# Emitter.net
KiCad netlist of a schematic drawn in Altium Designer
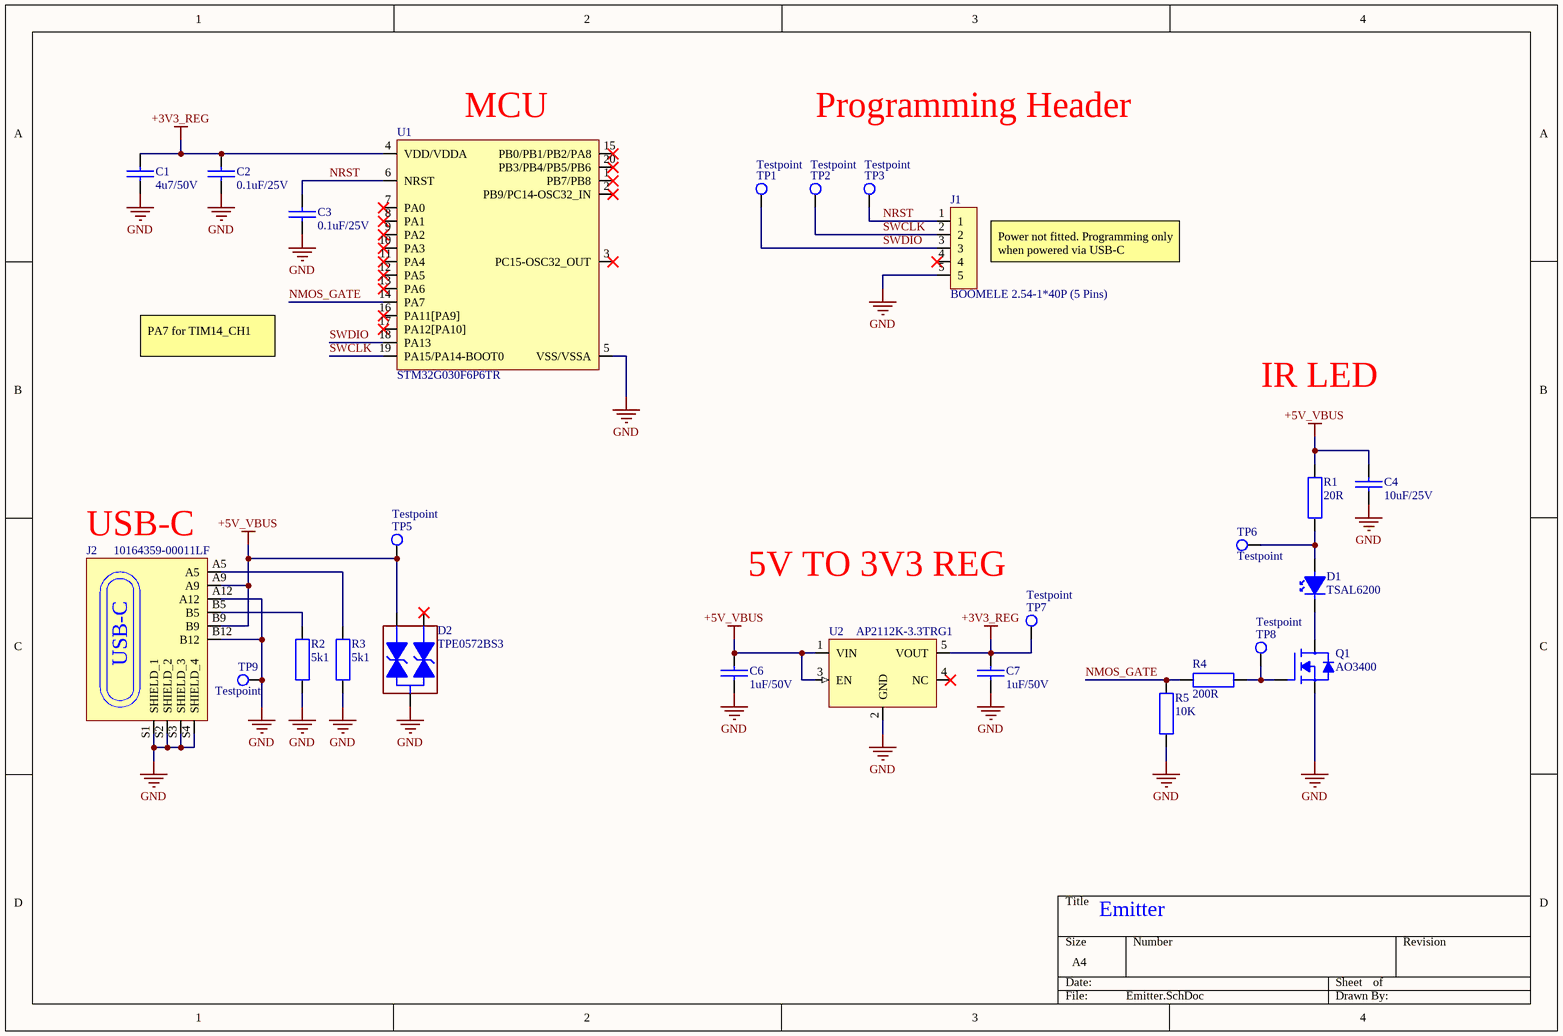
[diagram p0: Emitter.SchDoc]

(export (version "E")
  (design (tool "Eeschema 10.0.6"))
  (components
    (comp (ref "C1")
      (value "4u7/50V")
      (footprint "CAPC2012X95N")
      (description "CAP CER 4.7uF 50V X5R 0805")
      (fields
        (field (name "MANUFACTURER PART NUMBER") "CL21A475KBQNNNE")
        (field (name "MANUFACTURER") "Samsung Electro-Mechanics")
      )
      (libsource (lib "AltiumLibraries") (part "CL21A475KBQNNNE"))
    )
    (comp (ref "C2")
      (value "0.1uF/25V")
      (footprint "CAPC2012X95N")
      (description "CAP CER 0.1UF 25V X7R 0805")
      (fields
        (field (name "MANUFACTURER PART NUMBER") "CC0805KRX7R8BB104")
        (field (name "MANUFACTURER") "Yageo")
      )
      (libsource (lib "AltiumLibraries") (part "CC0805KRX7R8BB104"))
    )
    (comp (ref "C3")
      (value "0.1uF/25V")
      (footprint "CAPC2012X95N")
      (description "CAP CER 0.1UF 25V X7R 0805")
      (fields
        (field (name "MANUFACTURER PART NUMBER") "CC0805KRX7R8BB104")
        (field (name "MANUFACTURER") "Yageo")
      )
      (libsource (lib "AltiumLibraries") (part "CC0805KRX7R8BB104"))
    )
    (comp (ref "C4")
      (value "10uF/25V")
      (footprint "CAPC2012X95N")
      (description "CAP CER 10uF 25V X7R 0805")
      (fields
        (field (name "MANUFACTURER PART NUMBER") "CL21B106KAYQNNE")
        (field (name "MANUFACTURER") "Samsung Electro-Mechanics")
      )
      (libsource (lib "AltiumLibraries") (part "CL21B106KAYQNNE"))
    )
    (comp (ref "C6")
      (value "1uF/50V")
      (footprint "CAPC2012X95N")
      (description "CAP CER 1UF 50V X7R 0805")
      (fields
        (field (name "MANUFACTURER PART NUMBER") "CC0805KKX7R9BB105")
        (field (name "MANUFACTURER") "Yageo")
      )
      (libsource (lib "AltiumLibraries") (part "CC0805KKX7R9BB105"))
    )
    (comp (ref "C7")
      (value "1uF/50V")
      (footprint "CAPC2012X95N")
      (description "CAP CER 1UF 50V X7R 0805")
      (fields
        (field (name "MANUFACTURER PART NUMBER") "CC0805KKX7R9BB105")
        (field (name "MANUFACTURER") "Yageo")
      )
      (libsource (lib "AltiumLibraries") (part "CC0805KKX7R9BB105"))
    )
    (comp (ref "D1")
      (value "TSAL6200")
      (footprint "TSAL6200")
      (description "Infrared (IR) Emitter 940nm 1.35V 100mA 40mW/sr @ 100mA 34° Radial, 5mm Dia (T 1 3/4)")
      (fields (field (name "MANUFACTURER") "Vishay"))
      (libsource (lib "AltiumLibraries") (part "TSAL6200"))
    )
    (comp (ref "D2")
      (value "TPE0572BS3")
      (footprint "SOT95P240X115-3N")
      (description "ESD DIODE 5VWM 6VC 10VC SOT-23")
      (fields (field (name "MANUFACTURER") "TECH PUBLIC") (field (name "LCSC PART NUMBER") "C2858713"))
      (libsource (lib "AltiumLibraries") (part "TPE0572BS3"))
    )
    (comp (ref "J1")
      (value "BOOMELE 2.54-1*40P (5 Pins)")
      (footprint "HDRV_1X05_P254")
      (description "CONN HEADER 40POS 2.54mm SINGLE ROW TH (5 Pins Only)")
      (fields
        (field (name "MANUFACTURER PART NUMBER") "2.54-1*40P")
        (field (name "LCSC PART NUMBER") "C2337")
      )
      (libsource (lib "AltiumLibraries") (part "BOOMELE 2.54-1*40P (5 Pins Only)"))
    )
    (comp (ref "J2")
      (value "10164359-00011LF")
      (footprint "10164359-00011LF")
      (fields (field (name "MANUFACTURER") "Amphenol ICC (FCI)"))
      (libsource (lib "AltiumLibraries") (part "10164359-00011LF"))
    )
    (comp (ref "Q1")
      (value "AO3400")
      (footprint "SOT95P240X115-3N")
      (description "MOSFET N-CH 30V 5.8A SOT-23")
      (fields (field (name "LCSC PART NUMBER") "C181090") (field (name "MANUFACTURER") "Guangdong Hottech"))
      (libsource (lib "AltiumLibraries") (part "AO3400"))
    )
    (comp (ref "R1")
      (value "20R")
      (footprint "RESC3116X65N")
      (description "RES 20 OHM 1% 1/4W 1206")
      (fields
        (field (name "MANUFACTURER PART NUMBER") "RC1206FR-0720RL")
        (field (name "MANUFACTURER") "Yageo")
      )
      (libsource (lib "AltiumLibraries") (part "RC1206FR-0720RL"))
    )
    (comp (ref "R2")
      (value "5k1")
      (footprint "RESC2012X60N")
      (description "RES 5.1K OHM 1% 1/8W 0805")
      (fields
        (field (name "MANUFACTURER PART NUMBER") "RC0805FR-075K1L")
        (field (name "MANUFACTURER") "Yageo")
      )
      (libsource (lib "AltiumLibraries") (part "RC0805FR-075K1L"))
    )
    (comp (ref "R3")
      (value "5k1")
      (footprint "RESC2012X60N")
      (description "RES 5.1K OHM 1% 1/8W 0805")
      (fields
        (field (name "MANUFACTURER PART NUMBER") "RC0805FR-075K1L")
        (field (name "MANUFACTURER") "Yageo")
      )
      (libsource (lib "AltiumLibraries") (part "RC0805FR-075K1L"))
    )
    (comp (ref "R4")
      (value "200R")
      (footprint "RESC2012X60N")
      (description "RES 200Ω ±1% 125mW 0805")
      (fields
        (field (name "MANUFACTURER PART NUMBER") "RC0805FR-07200RL")
        (field (name "MANUFACTURER") "Yageo")
      )
      (libsource (lib "AltiumLibraries") (part "RC0805FR-07200RL"))
    )
    (comp (ref "R5")
      (value "10K")
      (footprint "RESC2012X60N")
      (description "RES SMD 10K OHM 0.1% 1/8W 0805")
      (fields
        (field (name "MANUFACTURER PART NUMBER") "RT0805BRD0710KL")
        (field (name "MANUFACTURER") "Yageo")
      )
      (libsource (lib "AltiumLibraries") (part "RT0805BRD0710KL"))
    )
    (comp (ref "TP1")
      (value "Testpoint")
      (footprint "TP_SMD_R1M0")
      (libsource (lib "AltiumLibraries") (part "Testpoint"))
    )
    (comp (ref "TP2")
      (value "Testpoint")
      (footprint "TP_SMD_R1M0")
      (libsource (lib "AltiumLibraries") (part "Testpoint"))
    )
    (comp (ref "TP3")
      (value "Testpoint")
      (footprint "TP_SMD_R1M0")
      (libsource (lib "AltiumLibraries") (part "Testpoint"))
    )
    (comp (ref "TP5")
      (value "Testpoint")
      (footprint "TP_SMD_R1M0")
      (libsource (lib "AltiumLibraries") (part "Testpoint"))
    )
    (comp (ref "TP6")
      (value "Testpoint")
      (footprint "TP_SMD_R1M0")
      (libsource (lib "AltiumLibraries") (part "Testpoint"))
    )
    (comp (ref "TP7")
      (value "Testpoint")
      (footprint "TP_SMD_R1M0")
      (libsource (lib "AltiumLibraries") (part "Testpoint"))
    )
    (comp (ref "TP8")
      (value "Testpoint")
      (footprint "TP_SMD_R1M0")
      (libsource (lib "AltiumLibraries") (part "Testpoint"))
    )
    (comp (ref "TP9")
      (value "Testpoint")
      (footprint "TP_SMD_R1M0")
      (libsource (lib "AltiumLibraries") (part "Testpoint"))
    )
    (comp (ref "U1")
      (value "STM32G030F6P6TR")
      (footprint "TSOP65P640X120-20N")
      (description "IC MCU 32BIT 32KB FLASH 20TSSOP")
      (fields (field (name "MANUFACTURER") "STMicroelectronics"))
      (libsource (lib "AltiumLibraries") (part "STM32G030F6P6TR"))
    )
    (comp (ref "U2")
      (value "AP2112K-3.3TRG1")
      (footprint "SOT95P285X140-5N")
      (description "IC REG LINEAR 3.3V 600MA SOT-25")
      (fields (field (name "MANUFACTURER") "Diodes Incorporated") (field (name "LCSC PART NUMBER") "C51118"))
      (libsource (lib "AltiumLibraries") (part "AP2112K-3.3TRG1"))
    )
  )
  (nets
    (net (code "1") (name "+3V3_REG") (class "Default")
      (node (ref "C1") (pin "2") (pinfunction "2_2") (pintype "passive"))
      (node (ref "C2") (pin "2") (pinfunction "2_2") (pintype "passive"))
      (node (ref "C7") (pin "2") (pinfunction "2_2") (pintype "passive"))
      (node (ref "TP7") (pin "1") (pinfunction "1_1") (pintype "passive"))
      (node (ref "U1") (pin "4") (pinfunction "VDD/VDDA_4") (pintype "power_in"))
      (node (ref "U2") (pin "5") (pinfunction "VOUT_5") (pintype "power_in"))
    )
    (net (code "2") (name "+5V_VBUS") (class "Default")
      (node (ref "C4") (pin "2") (pinfunction "2_2") (pintype "passive"))
      (node (ref "C6") (pin "2") (pinfunction "2_2") (pintype "passive"))
      (node (ref "D2") (pin "2") (pinfunction "2_2") (pintype "passive"))
      (node (ref "J2") (pin "A9") (pinfunction "A9_A9") (pintype "passive"))
      (node (ref "J2") (pin "B9") (pinfunction "B9_B9") (pintype "passive"))
      (node (ref "R1") (pin "2") (pinfunction "2_2") (pintype "passive"))
      (node (ref "TP5") (pin "1") (pinfunction "1_1") (pintype "passive"))
      (node (ref "U2") (pin "1") (pinfunction "VIN_1") (pintype "power_in"))
      (node (ref "U2") (pin "3") (pinfunction "EN_3") (pintype "input"))
    )
    (net (code "3") (name "/NMOS_GATE") (class "Default")
      (node (ref "R4") (pin "1") (pinfunction "1_1") (pintype "passive"))
      (node (ref "R5") (pin "2") (pinfunction "2_2") (pintype "passive"))
      (node (ref "U1") (pin "14") (pinfunction "PA7_14") (pintype "passive"))
    )
    (net (code "4") (name "/NRST") (class "Default")
      (node (ref "C3") (pin "2") (pinfunction "2_2") (pintype "passive"))
      (node (ref "J1") (pin "1") (pinfunction "1_1") (pintype "passive"))
      (node (ref "TP3") (pin "1") (pinfunction "1_1") (pintype "passive"))
      (node (ref "U1") (pin "6") (pinfunction "NRST_6") (pintype "passive"))
    )
    (net (code "5") (name "/SWCLK") (class "Default")
      (node (ref "J1") (pin "2") (pinfunction "2_2") (pintype "passive"))
      (node (ref "TP2") (pin "1") (pinfunction "1_1") (pintype "passive"))
      (node (ref "U1") (pin "19") (pinfunction "PA15/PA14-BOOT0_19") (pintype "passive"))
    )
    (net (code "6") (name "/SWDIO") (class "Default")
      (node (ref "J1") (pin "3") (pinfunction "3_3") (pintype "passive"))
      (node (ref "TP1") (pin "1") (pinfunction "1_1") (pintype "passive"))
      (node (ref "U1") (pin "18") (pinfunction "PA13_18") (pintype "passive"))
    )
    (net (code "7") (name "GND") (class "Default")
      (node (ref "C1") (pin "1") (pinfunction "1_1") (pintype "passive"))
      (node (ref "C2") (pin "1") (pinfunction "1_1") (pintype "passive"))
      (node (ref "C3") (pin "1") (pinfunction "1_1") (pintype "passive"))
      (node (ref "C4") (pin "1") (pinfunction "1_1") (pintype "passive"))
      (node (ref "C6") (pin "1") (pinfunction "1_1") (pintype "passive"))
      (node (ref "C7") (pin "1") (pinfunction "1_1") (pintype "passive"))
      (node (ref "D2") (pin "3") (pinfunction "GND_3") (pintype "passive"))
      (node (ref "J1") (pin "5") (pinfunction "5_5") (pintype "passive"))
      (node (ref "J2") (pin "A12") (pinfunction "A12_A12") (pintype "passive"))
      (node (ref "J2") (pin "B12") (pinfunction "B12_B12") (pintype "passive"))
      (node (ref "J2") (pin "S1") (pinfunction "SHIELD_1_S1") (pintype "passive"))
      (node (ref "J2") (pin "S2") (pinfunction "SHIELD_2_S2") (pintype "passive"))
      (node (ref "J2") (pin "S3") (pinfunction "SHIELD_3_S3") (pintype "passive"))
      (node (ref "J2") (pin "S4") (pinfunction "SHIELD_4_S4") (pintype "passive"))
      (node (ref "Q1") (pin "2") (pinfunction "2_2") (pintype "passive"))
      (node (ref "R2") (pin "1") (pinfunction "1_1") (pintype "passive"))
      (node (ref "R3") (pin "1") (pinfunction "1_1") (pintype "passive"))
      (node (ref "R5") (pin "1") (pinfunction "1_1") (pintype "passive"))
      (node (ref "TP9") (pin "1") (pinfunction "1_1") (pintype "passive"))
      (node (ref "U1") (pin "5") (pinfunction "VSS/VSSA_5") (pintype "power_in"))
      (node (ref "U2") (pin "2") (pinfunction "GND_2") (pintype "power_in"))
    )
    (net (code "8") (name "Net-(D1-Pad1)") (class "Default")
      (node (ref "D1") (pin "1") (pinfunction "1_1") (pintype "passive"))
      (node (ref "Q1") (pin "3") (pinfunction "3_3") (pintype "passive"))
    )
    (net (code "9") (name "Net-(D1-Pad2)") (class "Default")
      (node (ref "D1") (pin "2") (pinfunction "2_2") (pintype "passive"))
      (node (ref "R1") (pin "1") (pinfunction "1_1") (pintype "passive"))
      (node (ref "TP6") (pin "1") (pinfunction "1_1") (pintype "passive"))
    )
    (net (code "10") (name "Net-(J2-PadA5)") (class "Default")
      (node (ref "J2") (pin "A5") (pinfunction "A5_A5") (pintype "passive"))
      (node (ref "R3") (pin "2") (pinfunction "2_2") (pintype "passive"))
    )
    (net (code "11") (name "Net-(J2-PadB5)") (class "Default")
      (node (ref "J2") (pin "B5") (pinfunction "B5_B5") (pintype "passive"))
      (node (ref "R2") (pin "2") (pinfunction "2_2") (pintype "passive"))
    )
    (net (code "12") (name "Net-(Q1-Pad1)") (class "Default")
      (node (ref "Q1") (pin "1") (pinfunction "1_1") (pintype "passive"))
      (node (ref "R4") (pin "2") (pinfunction "2_2") (pintype "passive"))
      (node (ref "TP8") (pin "1") (pinfunction "1_1") (pintype "passive"))
    )
    (net (code "13") (name "unconnected-(D2-Pad1)") (class "Default")
      (node (ref "D2") (pin "1") (pinfunction "1_1") (pintype "passive+no_connect"))
    )
    (net (code "14") (name "unconnected-(J1-Pad4)") (class "Default")
      (node (ref "J1") (pin "4") (pinfunction "4_4") (pintype "passive+no_connect"))
    )
    (net (code "15") (name "unconnected-(U1-PA0-Pad7)") (class "Default")
      (node (ref "U1") (pin "7") (pinfunction "PA0_7") (pintype "passive+no_connect"))
    )
    (net (code "16") (name "unconnected-(U1-PA1-Pad8)") (class "Default")
      (node (ref "U1") (pin "8") (pinfunction "PA1_8") (pintype "passive+no_connect"))
    )
    (net (code "17") (name "unconnected-(U1-PA2-Pad9)") (class "Default")
      (node (ref "U1") (pin "9") (pinfunction "PA2_9") (pintype "passive+no_connect"))
    )
    (net (code "18") (name "unconnected-(U1-PA3-Pad10)") (class "Default")
      (node (ref "U1") (pin "10") (pinfunction "PA3_10") (pintype "passive+no_connect"))
    )
    (net (code "19") (name "unconnected-(U1-PA4-Pad11)") (class "Default")
      (node (ref "U1") (pin "11") (pinfunction "PA4_11") (pintype "passive+no_connect"))
    )
    (net (code "20") (name "unconnected-(U1-PA5-Pad12)") (class "Default")
      (node (ref "U1") (pin "12") (pinfunction "PA5_12") (pintype "passive+no_connect"))
    )
    (net (code "21") (name "unconnected-(U1-PA6-Pad13)") (class "Default")
      (node (ref "U1") (pin "13") (pinfunction "PA6_13") (pintype "passive+no_connect"))
    )
    (net (code "22") (name "unconnected-(U1-PA11[PA9]-Pad16)") (class "Default")
      (node (ref "U1") (pin "16") (pinfunction "PA11[PA9]_16") (pintype "passive+no_connect"))
    )
    (net (code "23") (name "unconnected-(U1-PA12[PA10]-Pad17)") (class "Default")
      (node (ref "U1") (pin "17") (pinfunction "PA12[PA10]_17") (pintype "passive+no_connect"))
    )
    (net (code "24") (name "unconnected-(U1-PB0{slash}PB1{slash}PB2{slash}PA8-Pad15)") (class "Default")
      (node (ref "U1") (pin "15") (pinfunction "PB0/PB1/PB2/PA8_15") (pintype "passive+no_connect"))
    )
    (net (code "25") (name "unconnected-(U1-PB3{slash}PB4{slash}PB5{slash}PB6-Pad20)") (class "Default")
      (node (ref "U1") (pin "20") (pinfunction "PB3/PB4/PB5/PB6_20") (pintype "passive+no_connect"))
    )
    (net (code "26") (name "unconnected-(U1-PB7{slash}PB8-Pad1)") (class "Default")
      (node (ref "U1") (pin "1") (pinfunction "PB7/PB8_1") (pintype "passive+no_connect"))
    )
    (net (code "27") (name "unconnected-(U1-PB9{slash}PC14-OSC32_IN-Pad2)") (class "Default")
      (node (ref "U1") (pin "2") (pinfunction "PB9/PC14-OSC32_IN_2") (pintype "passive+no_connect"))
    )
    (net (code "28") (name "unconnected-(U1-PC15-OSC32_OUT-Pad3)") (class "Default")
      (node (ref "U1") (pin "3") (pinfunction "PC15-OSC32_OUT_3") (pintype "passive+no_connect"))
    )
    (net (code "29") (name "unconnected-(U2-NC-Pad4)") (class "Default")
      (node (ref "U2") (pin "4") (pinfunction "NC_4") (pintype "passive+no_connect"))
    )
  )
)
